# SCH_CAN_Transceiver_TJA1050.net
KiCad netlist of a schematic drawn in Altium Designer
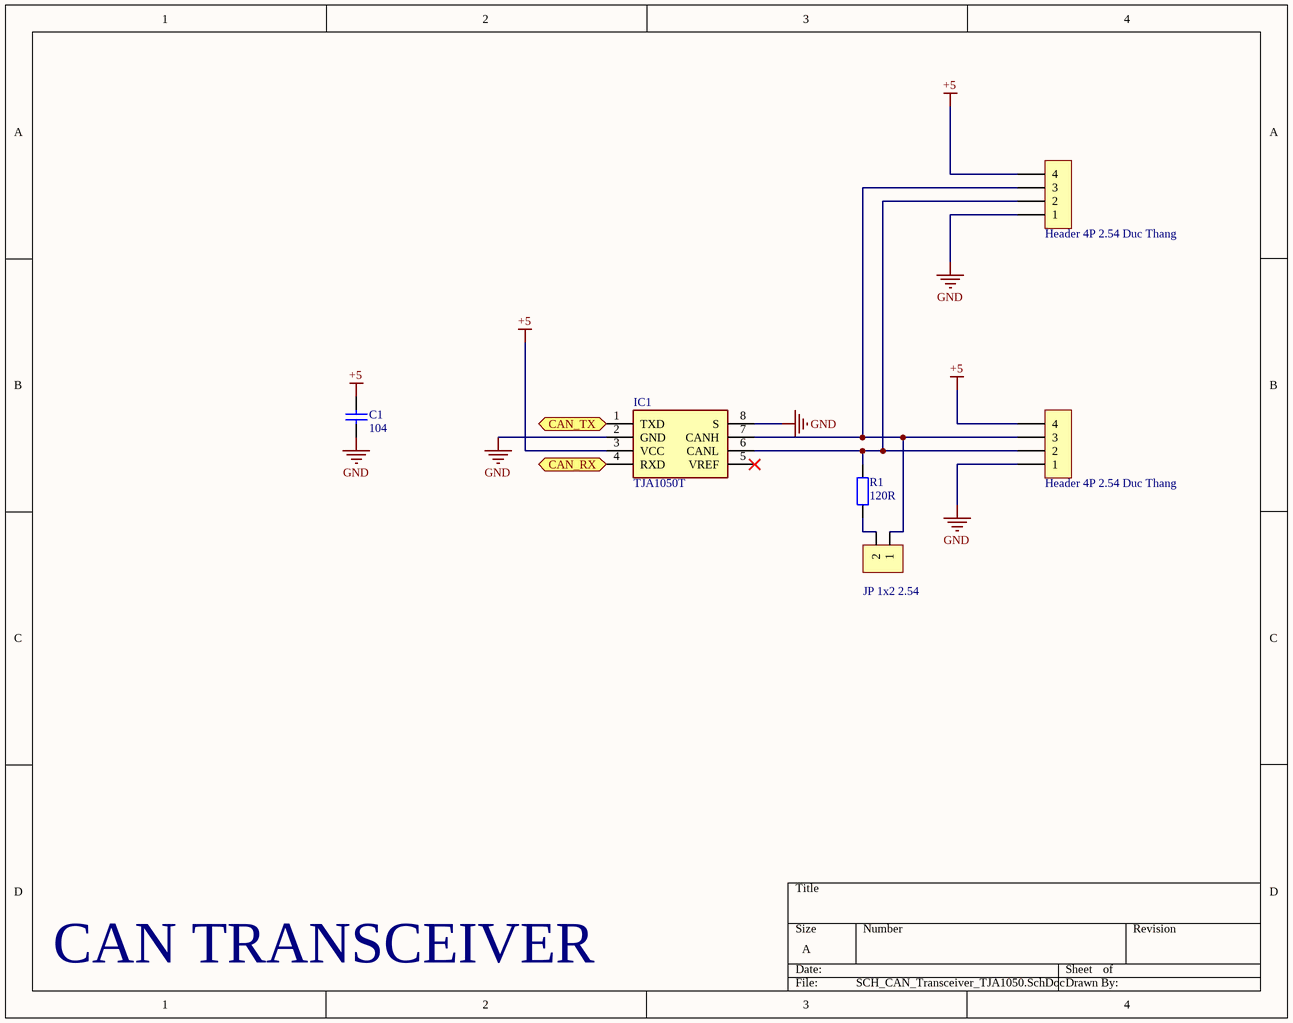
[diagram p0: SCH_CAN_Transceiver_TJA1050.SchDoc]

(export (version "E")
  (design (tool "Eeschema 10.0.6"))
  (components
    (comp (ref "C1")
      (value "104")
      (footprint "tu 0603")
      (description "Dán")
      (libsource (lib "Altium_Lib_by_KhueNguyenCreator") (part "Tu 0603 104 50V 10%"))
    )
    (comp (ref "H1")
      (value "Header 4P 2.54 Duc Thang")
      (footprint "XH2.54M-4")
      (description "Cắm")
      (libsource (lib "Altium_Lib_by_KhueNguyenCreator") (part "Header 4P 2.54 Duc Thang"))
    )
    (comp (ref "H2")
      (value "Header 4P 2.54 Duc Thang")
      (footprint "XH2.54M-4")
      (description "Cắm")
      (libsource (lib "Altium_Lib_by_KhueNguyenCreator") (part "Header 4P 2.54 Duc Thang"))
    )
    (comp (ref "IC1")
      (value "TJA1050T")
      (footprint "SamacSys:SOIC127P600X175-8N")
      (description "Integrated Circuit")
      (libsource (lib "*") (part "TJA1050T"))
    )
    (comp (ref "JP1")
      (value "JP 1x2 2.54")
      (footprint "JP 1x2 DT")
      (description "Cắm")
      (libsource (lib "Altium_Lib_by_KhueNguyenCreator") (part "JP 1x2 2.54 Duc Thang"))
    )
    (comp (ref "R1")
      (value "120R")
      (footprint "tro smd 0603")
      (description "Dán")
      (libsource (lib "Altium_Lib_by_KhueNguyenCreator") (part "Tro 0603 1% 0R"))
    )
  )
  (nets
    (net (code "1") (name "+5") (class "Default")
      (node (ref "C1") (pin "1") (pinfunction "1_1") (pintype "passive"))
      (node (ref "H1") (pin "4") (pinfunction "4_4") (pintype "passive"))
      (node (ref "H2") (pin "4") (pinfunction "4_4") (pintype "passive"))
      (node (ref "IC1") (pin "3") (pinfunction "VCC_3") (pintype "passive"))
    )
    (net (code "2") (name "/CAN_RX") (class "Default")
      (node (ref "IC1") (pin "4") (pinfunction "RXD_4") (pintype "passive"))
    )
    (net (code "3") (name "/CAN_TX") (class "Default")
      (node (ref "IC1") (pin "1") (pinfunction "TXD_1") (pintype "passive"))
    )
    (net (code "4") (name "GND") (class "Default")
      (node (ref "C1") (pin "2") (pinfunction "2_2") (pintype "passive"))
      (node (ref "H1") (pin "1") (pinfunction "1_1") (pintype "passive"))
      (node (ref "H2") (pin "1") (pinfunction "1_1") (pintype "passive"))
      (node (ref "IC1") (pin "2") (pinfunction "GND_2") (pintype "passive"))
      (node (ref "IC1") (pin "8") (pinfunction "S_8") (pintype "passive"))
    )
    (net (code "5") (name "Net-(IC1-CANH)") (class "Default")
      (node (ref "H1") (pin "3") (pinfunction "3_3") (pintype "passive"))
      (node (ref "H2") (pin "3") (pinfunction "3_3") (pintype "passive"))
      (node (ref "IC1") (pin "7") (pinfunction "CANH_7") (pintype "passive"))
      (node (ref "JP1") (pin "1") (pinfunction "1_1") (pintype "passive"))
    )
    (net (code "6") (name "Net-(IC1-CANL)") (class "Default")
      (node (ref "H1") (pin "2") (pinfunction "2_2") (pintype "passive"))
      (node (ref "H2") (pin "2") (pinfunction "2_2") (pintype "passive"))
      (node (ref "IC1") (pin "6") (pinfunction "CANL_6") (pintype "passive"))
      (node (ref "R1") (pin "2") (pinfunction "2_2") (pintype "passive"))
    )
    (net (code "7") (name "Net-(JP1-Pad2)") (class "Default")
      (node (ref "JP1") (pin "2") (pinfunction "2_2") (pintype "passive"))
      (node (ref "R1") (pin "1") (pinfunction "1_1") (pintype "passive"))
    )
    (net (code "8") (name "unconnected-(IC1-VREF-Pad5)") (class "Default")
      (node (ref "IC1") (pin "5") (pinfunction "VREF_5") (pintype "passive+no_connect"))
    )
  )
)
